# Fibernet.net
KiCad netlist of a schematic drawn in Altium Designer
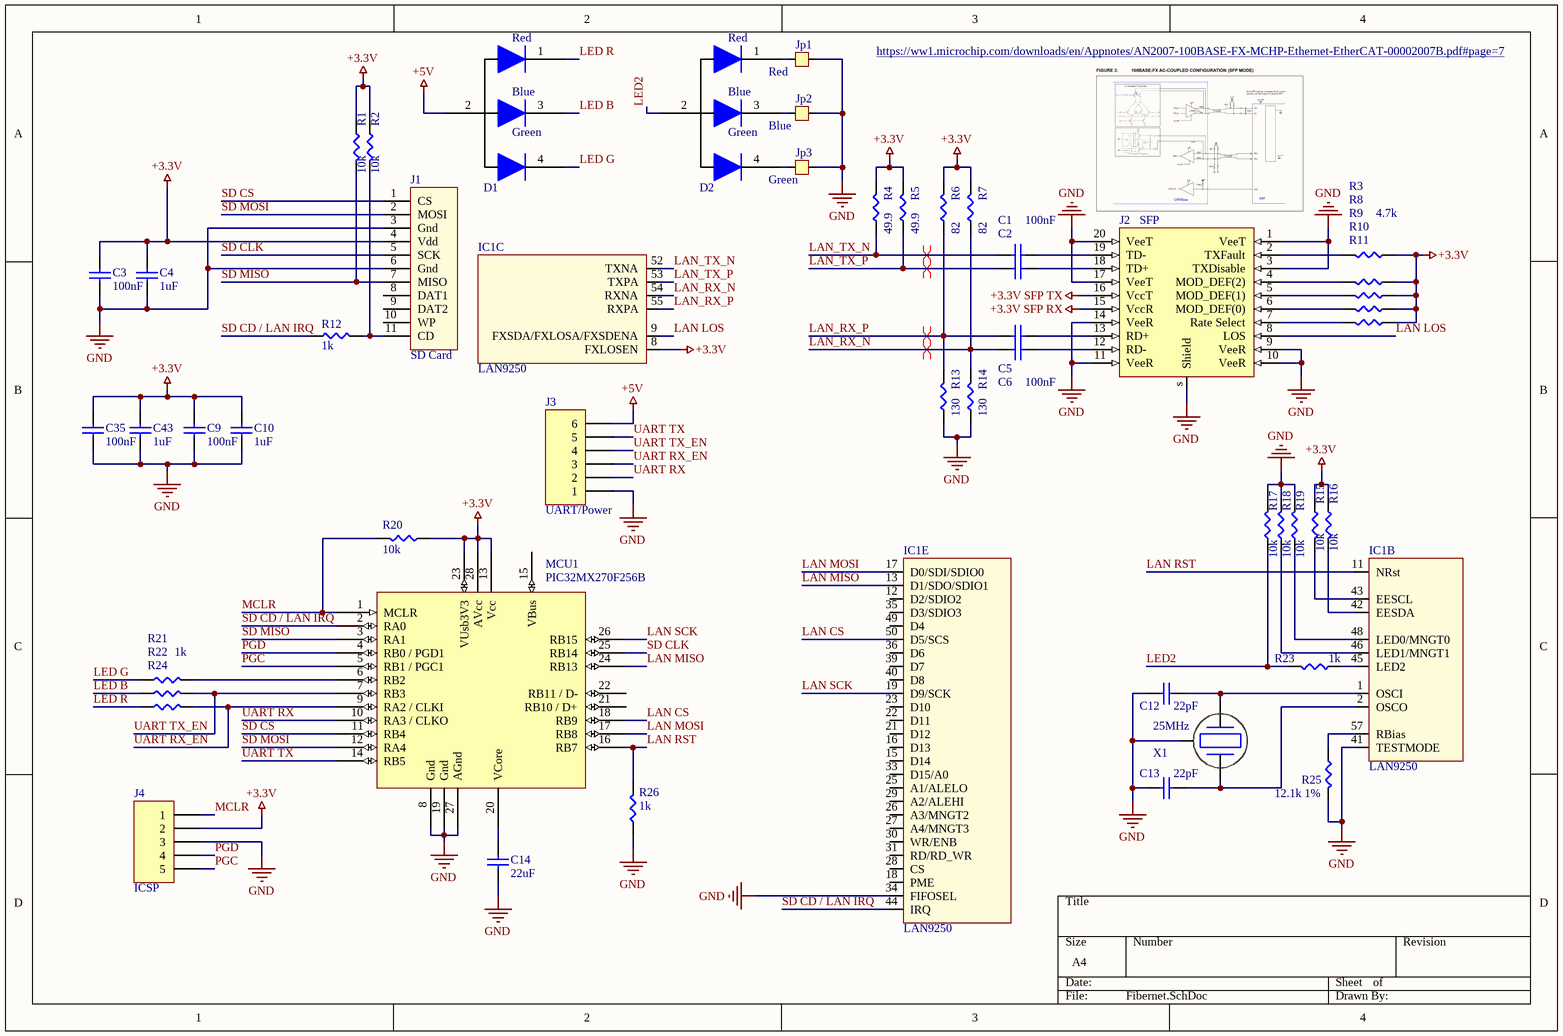
[diagram p0: Fibernet.SchDoc]

(export (version "E")
  (design (tool "Eeschema 10.0.6"))
  (components
    (comp (ref "C1") (value "100nF") (footprint "0402") (libsource (lib "stdLib") (part "Cap")))
    (comp (ref "C2") (value "100nF") (footprint "0402") (libsource (lib "stdLib") (part "Cap")))
    (comp (ref "C3") (value "100nF") (footprint "0402") (libsource (lib "stdLib") (part "Cap")))
    (comp (ref "C4") (value "1uF") (footprint "0402") (libsource (lib "stdLib") (part "Cap")))
    (comp (ref "C5") (value "100nF") (footprint "0402") (libsource (lib "stdLib") (part "Cap")))
    (comp (ref "C6") (value "100nF") (footprint "0402") (libsource (lib "stdLib") (part "Cap")))
    (comp (ref "C9") (value "100nF") (footprint "0402") (libsource (lib "stdLib") (part "Cap")))
    (comp (ref "C10") (value "1uF") (footprint "0402") (libsource (lib "stdLib") (part "Cap")))
    (comp (ref "C12") (value "22pF") (footprint "0402") (libsource (lib "stdLib") (part "Cap")))
    (comp (ref "C13") (value "22pF") (footprint "0402") (libsource (lib "stdLib") (part "Cap")))
    (comp (ref "C14") (value "22uF") (footprint "0603") (libsource (lib "stdLib") (part "Cap")))
    (comp (ref "C35") (value "100nF") (footprint "0402") (libsource (lib "stdLib") (part "Cap")))
    (comp (ref "C43") (value "1uF") (footprint "0402") (libsource (lib "stdLib") (part "Cap")))
    (comp (ref "D1")
      (value "RGB LED Common anode")
      (footprint "1411")
      (description "RGB LED Invered")
      (libsource (lib "stdLib") (part "RGB LED"))
    )
    (comp (ref "D2")
      (value "RGB LED Common anode")
      (footprint "1411")
      (description "RGB LED Invered")
      (libsource (lib "stdLib") (part "RGB LED"))
    )
    (comp (ref "IC1")
      (value "LAN9250")
      (footprint "QFN64")
      (description "10/100 Ethernet controller & PHY")
      (libsource (lib "") (part "LAN9250_1"))
    )
    (comp (ref "J1") (value "SD Card") (footprint "MEM2075") (libsource (lib "stdLib") (part "SD Card")))
    (comp (ref "J2")
      (value "SFP")
      (footprint "SFP Con and Cage")
      (description "SFP Connector with cage")
      (libsource (lib "stdLib") (part "SFP Connector"))
    )
    (comp (ref "J3")
      (value "UART/Power")
      (footprint "HDR1X6")
      (description "Header, 6-Pin")
      (fields (field (name "PUBLISHER") "Altium Limited"))
      (libsource (lib "Miscellaneous Connectors") (part "Header 6"))
    )
    (comp (ref "J4")
      (value "ICSP")
      (footprint "HDR1X5")
      (description "Header, 5-Pin")
      (fields (field (name "PUBLISHER") "Altium Limited"))
      (libsource (lib "Miscellaneous Connectors") (part "Header 5"))
    )
    (comp (ref "Jp1") (value "Red") (footprint "PCB Jumper NO") (libsource (lib "stdLib") (part "Jumper")))
    (comp (ref "Jp2") (value "Blue") (footprint "PCB Jumper NO") (libsource (lib "stdLib") (part "Jumper")))
    (comp (ref "Jp3") (value "Green") (footprint "PCB Jumper NO") (libsource (lib "stdLib") (part "Jumper")))
    (comp (ref "MCU1")
      (value "PIC32MX270F256B")
      (footprint "TSSOP28_Wide")
      (description "32Bit pic with usb")
      (libsource (lib "stdLib") (part "PIC32MX2xxFxxxB"))
    )
    (comp (ref "R1") (value "10k") (footprint "0402") (libsource (lib "stdLib") (part "Resistor")))
    (comp (ref "R2") (value "10k") (footprint "0402") (libsource (lib "stdLib") (part "Resistor")))
    (comp (ref "R3") (value "4.7k") (footprint "0402") (libsource (lib "stdLib") (part "Resistor")))
    (comp (ref "R4") (value "49.9") (footprint "0402") (libsource (lib "stdLib") (part "Resistor")))
    (comp (ref "R5") (value "49.9") (footprint "0402") (libsource (lib "stdLib") (part "Resistor")))
    (comp (ref "R6") (value "82") (footprint "0402") (libsource (lib "stdLib") (part "Resistor")))
    (comp (ref "R7") (value "82") (footprint "0402") (libsource (lib "stdLib") (part "Resistor")))
    (comp (ref "R8") (value "4.7k") (footprint "0402") (libsource (lib "stdLib") (part "Resistor")))
    (comp (ref "R9") (value "4.7k") (footprint "0402") (libsource (lib "stdLib") (part "Resistor")))
    (comp (ref "R10") (value "4.7k") (footprint "0402") (libsource (lib "stdLib") (part "Resistor")))
    (comp (ref "R11") (value "4.7k") (footprint "0402") (libsource (lib "stdLib") (part "Resistor")))
    (comp (ref "R12") (value "1k") (footprint "0402") (libsource (lib "stdLib") (part "Resistor")))
    (comp (ref "R13") (value "130") (footprint "0402") (libsource (lib "stdLib") (part "Resistor")))
    (comp (ref "R14") (value "130") (footprint "0402") (libsource (lib "stdLib") (part "Resistor")))
    (comp (ref "R15") (value "10k") (footprint "0402") (libsource (lib "stdLib") (part "Resistor")))
    (comp (ref "R16") (value "10k") (footprint "0402") (libsource (lib "stdLib") (part "Resistor")))
    (comp (ref "R17") (value "10k") (footprint "0402") (libsource (lib "stdLib") (part "Resistor")))
    (comp (ref "R18") (value "10k") (footprint "0402") (libsource (lib "stdLib") (part "Resistor")))
    (comp (ref "R19") (value "10k") (footprint "0402") (libsource (lib "stdLib") (part "Resistor")))
    (comp (ref "R20") (value "10k") (footprint "0402") (libsource (lib "stdLib") (part "Resistor")))
    (comp (ref "R21") (value "1k") (footprint "0402") (libsource (lib "stdLib") (part "Resistor")))
    (comp (ref "R22") (value "1k") (footprint "0402") (libsource (lib "stdLib") (part "Resistor")))
    (comp (ref "R23") (value "1k") (footprint "0402") (libsource (lib "stdLib") (part "Resistor")))
    (comp (ref "R24") (value "1k") (footprint "0402") (libsource (lib "stdLib") (part "Resistor")))
    (comp (ref "R25") (value "12.1k 1%") (footprint "0402") (libsource (lib "stdLib") (part "Resistor")))
    (comp (ref "R26") (value "1k") (footprint "0402") (libsource (lib "stdLib") (part "Resistor")))
    (comp (ref "X1")
      (value "25MHz")
      (footprint "ECS-3225MV Oscillator")
      (libsource (lib "stdLib") (part "Quarz crystal"))
    )
  )
  (nets
    (net (code "1") (name "+3.3V") (class "Default")
      (node (ref "C10") (pin "2") (pinfunction "2_2") (pintype "passive"))
      (node (ref "C3") (pin "2") (pinfunction "2_2") (pintype "passive"))
      (node (ref "C35") (pin "2") (pinfunction "2_2") (pintype "passive"))
      (node (ref "C4") (pin "2") (pinfunction "2_2") (pintype "passive"))
      (node (ref "C43") (pin "2") (pinfunction "2_2") (pintype "passive"))
      (node (ref "C9") (pin "2") (pinfunction "2_2") (pintype "passive"))
      (node (ref "IC1") (pin "8") (pinfunction "FXLOSEN_8") (pintype "passive"))
      (node (ref "J1") (pin "4") (pinfunction "Vdd_4") (pintype "passive"))
      (node (ref "J4") (pin "2") (pinfunction "2_2") (pintype "passive"))
      (node (ref "MCU1") (pin "13") (pinfunction "Vcc_13") (pintype "power_in"))
      (node (ref "MCU1") (pin "23") (pinfunction "VUsb3V3_23") (pintype "bidirectional"))
      (node (ref "MCU1") (pin "28") (pinfunction "AVcc_28") (pintype "power_in"))
      (node (ref "R1") (pin "1") (pinfunction "1_1") (pintype "passive"))
      (node (ref "R10") (pin "2") (pinfunction "2_2") (pintype "passive"))
      (node (ref "R11") (pin "2") (pinfunction "2_2") (pintype "passive"))
      (node (ref "R15") (pin "1") (pinfunction "1_1") (pintype "passive"))
      (node (ref "R16") (pin "1") (pinfunction "1_1") (pintype "passive"))
      (node (ref "R2") (pin "1") (pinfunction "1_1") (pintype "passive"))
      (node (ref "R20") (pin "1") (pinfunction "1_1") (pintype "passive"))
      (node (ref "R3") (pin "2") (pinfunction "2_2") (pintype "passive"))
      (node (ref "R4") (pin "1") (pinfunction "1_1") (pintype "passive"))
      (node (ref "R5") (pin "1") (pinfunction "1_1") (pintype "passive"))
      (node (ref "R6") (pin "1") (pinfunction "1_1") (pintype "passive"))
      (node (ref "R7") (pin "1") (pinfunction "1_1") (pintype "passive"))
      (node (ref "R8") (pin "2") (pinfunction "2_2") (pintype "passive"))
      (node (ref "R9") (pin "2") (pinfunction "2_2") (pintype "passive"))
    )
    (net (code "2") (name "+3.3V SFP RX") (class "Default")
      (node (ref "J2") (pin "15") (pinfunction "VccR_15") (pintype "input"))
    )
    (net (code "3") (name "+3.3V SFP TX") (class "Default")
      (node (ref "J2") (pin "16") (pinfunction "VccT_16") (pintype "input"))
    )
    (net (code "4") (name "+5V") (class "Default")
      (node (ref "D1") (pin "2") (pintype "passive"))
      (node (ref "J3") (pin "6") (pinfunction "6_6") (pintype "passive"))
    )
    (net (code "5") (name "/LAN CS") (class "Default")
      (node (ref "IC1") (pin "50") (pinfunction "D5/SCS_50") (pintype "passive"))
      (node (ref "MCU1") (pin "18") (pinfunction "RB9_18") (pintype "bidirectional"))
    )
    (net (code "6") (name "/LAN LOS") (class "Default")
      (node (ref "IC1") (pin "9") (pinfunction "FXSDA/FXLOSA/FXSDENA_9") (pintype "passive"))
      (node (ref "J2") (pin "8") (pinfunction "LOS_8") (pintype "input"))
    )
    (net (code "7") (name "/LAN MISO") (class "Default")
      (node (ref "IC1") (pin "13") (pinfunction "D1/SDO/SDIO1_13") (pintype "passive"))
      (node (ref "MCU1") (pin "24") (pinfunction "RB13_24") (pintype "bidirectional"))
    )
    (net (code "8") (name "/LAN MOSI") (class "Default")
      (node (ref "IC1") (pin "17") (pinfunction "D0/SDI/SDIO0_17") (pintype "passive"))
      (node (ref "MCU1") (pin "17") (pinfunction "RB8_17") (pintype "bidirectional"))
    )
    (net (code "9") (name "/LAN RST") (class "Default")
      (node (ref "IC1") (pin "11") (pinfunction "NRst_11") (pintype "passive"))
      (node (ref "MCU1") (pin "16") (pinfunction "RB7_16") (pintype "bidirectional"))
      (node (ref "R26") (pin "1") (pinfunction "1_1") (pintype "passive"))
    )
    (net (code "10") (name "/LAN SCK") (class "Default")
      (node (ref "IC1") (pin "19") (pinfunction "D9/SCK_19") (pintype "passive"))
      (node (ref "MCU1") (pin "26") (pinfunction "RB15_26") (pintype "bidirectional"))
    )
    (net (code "11") (name "/LAN_RX_N") (class "Default")
      (node (ref "C6") (pin "1") (pinfunction "1_1") (pintype "passive"))
      (node (ref "IC1") (pin "54") (pinfunction "RXNA_54") (pintype "passive"))
      (node (ref "R14") (pin "1") (pinfunction "1_1") (pintype "passive"))
      (node (ref "R7") (pin "2") (pinfunction "2_2") (pintype "passive"))
    )
    (net (code "12") (name "/LAN_RX_P") (class "Default")
      (node (ref "C5") (pin "1") (pinfunction "1_1") (pintype "passive"))
      (node (ref "IC1") (pin "55") (pinfunction "RXPA_55") (pintype "passive"))
      (node (ref "R13") (pin "1") (pinfunction "1_1") (pintype "passive"))
      (node (ref "R6") (pin "2") (pinfunction "2_2") (pintype "passive"))
    )
    (net (code "13") (name "/LAN_TX_N") (class "Default")
      (node (ref "C1") (pin "1") (pinfunction "1_1") (pintype "passive"))
      (node (ref "IC1") (pin "52") (pinfunction "TXNA_52") (pintype "passive"))
      (node (ref "R4") (pin "2") (pinfunction "2_2") (pintype "passive"))
    )
    (net (code "14") (name "/LAN_TX_P") (class "Default")
      (node (ref "C2") (pin "1") (pinfunction "1_1") (pintype "passive"))
      (node (ref "IC1") (pin "53") (pinfunction "TXPA_53") (pintype "passive"))
      (node (ref "R5") (pin "2") (pinfunction "2_2") (pintype "passive"))
    )
    (net (code "15") (name "/LED B") (class "Default")
      (node (ref "D1") (pin "3") (pintype "passive"))
      (node (ref "R22") (pin "2") (pinfunction "2_2") (pintype "passive"))
    )
    (net (code "16") (name "/LED G") (class "Default")
      (node (ref "D1") (pin "4") (pintype "passive"))
      (node (ref "R21") (pin "2") (pinfunction "2_2") (pintype "passive"))
    )
    (net (code "17") (name "/LED R") (class "Default")
      (node (ref "D1") (pin "1") (pintype "passive"))
      (node (ref "R24") (pin "2") (pinfunction "2_2") (pintype "passive"))
    )
    (net (code "18") (name "/LED2") (class "Default")
      (node (ref "D2") (pin "2") (pintype "passive"))
      (node (ref "R17") (pin "2") (pinfunction "2_2") (pintype "passive"))
      (node (ref "R23") (pin "1") (pinfunction "1_1") (pintype "passive"))
    )
    (net (code "19") (name "/MCLR") (class "Default")
      (node (ref "J4") (pin "1") (pinfunction "1_1") (pintype "passive"))
      (node (ref "MCU1") (pin "1") (pinfunction "MCLR_1") (pintype "input"))
      (node (ref "R20") (pin "2") (pinfunction "2_2") (pintype "passive"))
    )
    (net (code "20") (name "/PGC") (class "Default")
      (node (ref "J4") (pin "5") (pinfunction "5_5") (pintype "passive"))
      (node (ref "MCU1") (pin "5") (pinfunction "RB1_/_PGC1_5") (pintype "bidirectional"))
    )
    (net (code "21") (name "/PGD") (class "Default")
      (node (ref "J4") (pin "4") (pinfunction "4_4") (pintype "passive"))
      (node (ref "MCU1") (pin "4") (pinfunction "RB0_/_PGD1_4") (pintype "bidirectional"))
    )
    (net (code "22") (name "/SD CD {slash} LAN IRQ") (class "Default")
      (node (ref "IC1") (pin "44") (pinfunction "IRQ_44") (pintype "passive"))
      (node (ref "MCU1") (pin "2") (pinfunction "RA0_2") (pintype "bidirectional"))
      (node (ref "R12") (pin "1") (pinfunction "1_1") (pintype "passive"))
    )
    (net (code "23") (name "/SD CLK") (class "Default")
      (node (ref "J1") (pin "5") (pinfunction "SCK_5") (pintype "passive"))
      (node (ref "MCU1") (pin "25") (pinfunction "RB14_25") (pintype "bidirectional"))
    )
    (net (code "24") (name "/SD CS") (class "Default")
      (node (ref "J1") (pin "1") (pinfunction "CS_1") (pintype "passive"))
      (node (ref "MCU1") (pin "11") (pinfunction "RB4_11") (pintype "bidirectional"))
    )
    (net (code "25") (name "/SD MISO") (class "Default")
      (node (ref "J1") (pin "7") (pinfunction "MISO_7") (pintype "passive"))
      (node (ref "MCU1") (pin "3") (pinfunction "RA1_3") (pintype "bidirectional"))
      (node (ref "R1") (pin "2") (pinfunction "2_2") (pintype "passive"))
    )
    (net (code "26") (name "/SD MOSI") (class "Default")
      (node (ref "J1") (pin "2") (pinfunction "MOSI_2") (pintype "passive"))
      (node (ref "MCU1") (pin "12") (pinfunction "RA4_12") (pintype "bidirectional"))
    )
    (net (code "27") (name "/UART RX") (class "Default")
      (node (ref "J3") (pin "2") (pinfunction "2_2") (pintype "passive"))
      (node (ref "MCU1") (pin "10") (pinfunction "RA3_/_CLKO_10") (pintype "bidirectional"))
    )
    (net (code "28") (name "/UART RX_EN") (class "Default")
      (node (ref "J3") (pin "3") (pinfunction "3_3") (pintype "passive"))
      (node (ref "MCU1") (pin "9") (pinfunction "RA2_/_CLKI_9") (pintype "bidirectional"))
      (node (ref "R24") (pin "1") (pinfunction "1_1") (pintype "passive"))
    )
    (net (code "29") (name "/UART TX") (class "Default")
      (node (ref "J3") (pin "5") (pinfunction "5_5") (pintype "passive"))
      (node (ref "MCU1") (pin "14") (pinfunction "RB5_14") (pintype "bidirectional"))
    )
    (net (code "30") (name "/UART TX_EN") (class "Default")
      (node (ref "J3") (pin "4") (pinfunction "4_4") (pintype "passive"))
      (node (ref "MCU1") (pin "7") (pinfunction "RB3_7") (pintype "bidirectional"))
      (node (ref "R22") (pin "1") (pinfunction "1_1") (pintype "passive"))
    )
    (net (code "31") (name "GND") (class "Default")
      (node (ref "C10") (pin "1") (pinfunction "1_1") (pintype "passive"))
      (node (ref "C12") (pin "1") (pinfunction "1_1") (pintype "passive"))
      (node (ref "C13") (pin "1") (pinfunction "1_1") (pintype "passive"))
      (node (ref "C14") (pin "1") (pinfunction "1_1") (pintype "passive"))
      (node (ref "C3") (pin "1") (pinfunction "1_1") (pintype "passive"))
      (node (ref "C35") (pin "1") (pinfunction "1_1") (pintype "passive"))
      (node (ref "C4") (pin "1") (pinfunction "1_1") (pintype "passive"))
      (node (ref "C43") (pin "1") (pinfunction "1_1") (pintype "passive"))
      (node (ref "C9") (pin "1") (pinfunction "1_1") (pintype "passive"))
      (node (ref "IC1") (pin "34") (pinfunction "FIFOSEL_34") (pintype "passive"))
      (node (ref "IC1") (pin "41") (pinfunction "TESTMODE_41") (pintype "passive"))
      (node (ref "J1") (pin "3") (pinfunction "Gnd_3") (pintype "passive"))
      (node (ref "J1") (pin "6") (pinfunction "Gnd_6") (pintype "passive"))
      (node (ref "J2") (pin "1") (pinfunction "VeeT_1") (pintype "input"))
      (node (ref "J2") (pin "10") (pinfunction "VeeR_10") (pintype "input"))
      (node (ref "J2") (pin "11") (pinfunction "VeeR_11") (pintype "input"))
      (node (ref "J2") (pin "14") (pinfunction "VeeR_14") (pintype "input"))
      (node (ref "J2") (pin "17") (pinfunction "VeeT_17") (pintype "input"))
      (node (ref "J2") (pin "20") (pinfunction "VeeT_20") (pintype "input"))
      (node (ref "J2") (pin "3") (pinfunction "TXDisable_3") (pintype "input"))
      (node (ref "J2") (pin "9") (pinfunction "VeeR_9") (pintype "input"))
      (node (ref "J2") (pin "s") (pinfunction "Shield_s") (pintype "passive"))
      (node (ref "J3") (pin "1") (pinfunction "1_1") (pintype "passive"))
      (node (ref "J4") (pin "3") (pinfunction "3_3") (pintype "passive"))
      (node (ref "Jp1") (pin "2") (pinfunction "2_2") (pintype "passive"))
      (node (ref "Jp2") (pin "2") (pinfunction "2_2") (pintype "passive"))
      (node (ref "Jp3") (pin "2") (pinfunction "2_2") (pintype "passive"))
      (node (ref "MCU1") (pin "19") (pinfunction "Gnd_19") (pintype "power_in"))
      (node (ref "MCU1") (pin "27") (pinfunction "AGnd_27") (pintype "power_in"))
      (node (ref "MCU1") (pin "8") (pinfunction "Gnd_8") (pintype "power_in"))
      (node (ref "R13") (pin "2") (pinfunction "2_2") (pintype "passive"))
      (node (ref "R14") (pin "2") (pinfunction "2_2") (pintype "passive"))
      (node (ref "R17") (pin "1") (pinfunction "1_1") (pintype "passive"))
      (node (ref "R18") (pin "1") (pinfunction "1_1") (pintype "passive"))
      (node (ref "R19") (pin "1") (pinfunction "1_1") (pintype "passive"))
      (node (ref "R25") (pin "1") (pinfunction "1_1") (pintype "passive"))
      (node (ref "R26") (pin "2") (pinfunction "2_2") (pintype "passive"))
      (node (ref "X1") (pin "3") (pinfunction "Shield_3") (pintype "passive"))
    )
    (net (code "32") (name "Net-(D2-Pad1)") (class "Default")
      (node (ref "D2") (pin "1") (pintype "passive"))
      (node (ref "Jp1") (pin "1") (pinfunction "1_1") (pintype "passive"))
    )
    (net (code "33") (name "Net-(D2-Pad3)") (class "Default")
      (node (ref "D2") (pin "3") (pintype "passive"))
      (node (ref "Jp2") (pin "1") (pinfunction "1_1") (pintype "passive"))
    )
    (net (code "34") (name "Net-(D2-Pad4)") (class "Default")
      (node (ref "D2") (pin "4") (pintype "passive"))
      (node (ref "Jp3") (pin "1") (pinfunction "1_1") (pintype "passive"))
    )
    (net (code "35") (name "Net-(IC1B-EESCL)") (class "Default")
      (node (ref "IC1") (pin "43") (pinfunction "EESCL_43") (pintype "passive"))
      (node (ref "R15") (pin "2") (pinfunction "2_2") (pintype "passive"))
    )
    (net (code "36") (name "Net-(IC1B-EESDA)") (class "Default")
      (node (ref "IC1") (pin "42") (pinfunction "EESDA_42") (pintype "passive"))
      (node (ref "R16") (pin "2") (pinfunction "2_2") (pintype "passive"))
    )
    (net (code "37") (name "Net-(IC1B-LED0{slash}MNGT0)") (class "Default")
      (node (ref "IC1") (pin "48") (pinfunction "LED0/MNGT0_48") (pintype "passive"))
      (node (ref "R19") (pin "2") (pinfunction "2_2") (pintype "passive"))
    )
    (net (code "38") (name "Net-(IC1B-LED1{slash}MNGT1)") (class "Default")
      (node (ref "IC1") (pin "46") (pinfunction "LED1/MNGT1_46") (pintype "passive"))
      (node (ref "R18") (pin "2") (pinfunction "2_2") (pintype "passive"))
    )
    (net (code "39") (name "Net-(IC1B-LED2)") (class "Default")
      (node (ref "IC1") (pin "45") (pinfunction "LED2_45") (pintype "passive"))
      (node (ref "R23") (pin "2") (pinfunction "2_2") (pintype "passive"))
    )
    (net (code "40") (name "Net-(IC1B-OSCI)") (class "Default")
      (node (ref "C12") (pin "2") (pinfunction "2_2") (pintype "passive"))
      (node (ref "IC1") (pin "1") (pinfunction "OSCI_1") (pintype "passive"))
      (node (ref "X1") (pin "2") (pinfunction "24_2") (pintype "passive"))
    )
    (net (code "41") (name "Net-(IC1B-OSCO)") (class "Default")
      (node (ref "C13") (pin "2") (pinfunction "2_2") (pintype "passive"))
      (node (ref "IC1") (pin "2") (pinfunction "OSCO_2") (pintype "passive"))
      (node (ref "X1") (pin "1") (pinfunction "23_1") (pintype "passive"))
    )
    (net (code "42") (name "Net-(IC1B-RBias)") (class "Default")
      (node (ref "IC1") (pin "57") (pinfunction "RBias_57") (pintype "passive"))
      (node (ref "R25") (pin "2") (pinfunction "2_2") (pintype "passive"))
    )
    (net (code "43") (name "Net-(J1-CD)") (class "Default")
      (node (ref "J1") (pin "11") (pinfunction "CD_11") (pintype "passive"))
      (node (ref "R12") (pin "2") (pinfunction "2_2") (pintype "passive"))
      (node (ref "R2") (pin "2") (pinfunction "2_2") (pintype "passive"))
    )
    (net (code "44") (name "Net-(J2-MOD_DEF(0))") (class "Default")
      (node (ref "J2") (pin "6") (pinfunction "MOD_DEF(0)_6") (pintype "input"))
      (node (ref "R9") (pin "1") (pinfunction "1_1") (pintype "passive"))
    )
    (net (code "45") (name "Net-(J2-MOD_DEF(1))") (class "Default")
      (node (ref "J2") (pin "5") (pinfunction "MOD_DEF(1)_5") (pintype "input"))
      (node (ref "R8") (pin "1") (pinfunction "1_1") (pintype "passive"))
    )
    (net (code "46") (name "Net-(J2-MOD_DEF(2))") (class "Default")
      (node (ref "J2") (pin "4") (pinfunction "MOD_DEF(2)_4") (pintype "input"))
      (node (ref "R10") (pin "1") (pinfunction "1_1") (pintype "passive"))
    )
    (net (code "47") (name "Net-(J2-RD+)") (class "Default")
      (node (ref "C5") (pin "2") (pinfunction "2_2") (pintype "passive"))
      (node (ref "J2") (pin "13") (pinfunction "RD+_13") (pintype "input"))
    )
    (net (code "48") (name "Net-(J2-RD-)") (class "Default")
      (node (ref "C6") (pin "2") (pinfunction "2_2") (pintype "passive"))
      (node (ref "J2") (pin "12") (pinfunction "RD-_12") (pintype "input"))
    )
    (net (code "49") (name "Net-(J2-Rate_Select)") (class "Default")
      (node (ref "J2") (pin "7") (pinfunction "Rate_Select_7") (pintype "input"))
      (node (ref "R11") (pin "1") (pinfunction "1_1") (pintype "passive"))
    )
    (net (code "50") (name "Net-(J2-TD+)") (class "Default")
      (node (ref "C2") (pin "2") (pinfunction "2_2") (pintype "passive"))
      (node (ref "J2") (pin "18") (pinfunction "TD+_18") (pintype "input"))
    )
    (net (code "51") (name "Net-(J2-TD-)") (class "Default")
      (node (ref "C1") (pin "2") (pinfunction "2_2") (pintype "passive"))
      (node (ref "J2") (pin "19") (pinfunction "TD-_19") (pintype "input"))
    )
    (net (code "52") (name "Net-(J2-TXFault)") (class "Default")
      (node (ref "J2") (pin "2") (pinfunction "TXFault_2") (pintype "input"))
      (node (ref "R3") (pin "1") (pinfunction "1_1") (pintype "passive"))
    )
    (net (code "53") (name "Net-(MCU1-RB2)") (class "Default")
      (node (ref "MCU1") (pin "6") (pinfunction "RB2_6") (pintype "bidirectional"))
      (node (ref "R21") (pin "1") (pinfunction "1_1") (pintype "passive"))
    )
    (net (code "54") (name "Net-(MCU1-VCore)") (class "Default")
      (node (ref "C14") (pin "2") (pinfunction "2_2") (pintype "passive"))
      (node (ref "MCU1") (pin "20") (pinfunction "VCore_20") (pintype "power_in"))
    )
    (net (code "55") (name "unconnected-(IC1E-A1{slash}ALELO-Pad25)") (class "Default")
      (node (ref "IC1") (pin "25") (pinfunction "A1/ALELO_25") (pintype "passive"))
    )
    (net (code "56") (name "unconnected-(IC1E-A2{slash}ALEHI-Pad29)") (class "Default")
      (node (ref "IC1") (pin "29") (pinfunction "A2/ALEHI_29") (pintype "passive"))
    )
    (net (code "57") (name "unconnected-(IC1E-A3{slash}MNGT2-Pad26)") (class "Default")
      (node (ref "IC1") (pin "26") (pinfunction "A3/MNGT2_26") (pintype "passive"))
    )
    (net (code "58") (name "unconnected-(IC1E-A4{slash}MNGT3-Pad27)") (class "Default")
      (node (ref "IC1") (pin "27") (pinfunction "A4/MNGT3_27") (pintype "passive"))
    )
    (net (code "59") (name "unconnected-(IC1E-CS-Pad28)") (class "Default")
      (node (ref "IC1") (pin "28") (pinfunction "CS_28") (pintype "passive"))
    )
    (net (code "60") (name "unconnected-(IC1E-D2{slash}SDIO2-Pad12)") (class "Default")
      (node (ref "IC1") (pin "12") (pinfunction "D2/SDIO2_12") (pintype "passive"))
    )
    (net (code "61") (name "unconnected-(IC1E-D3{slash}SDIO3-Pad35)") (class "Default")
      (node (ref "IC1") (pin "35") (pinfunction "D3/SDIO3_35") (pintype "passive"))
    )
    (net (code "62") (name "unconnected-(IC1E-D4-Pad49)") (class "Default")
      (node (ref "IC1") (pin "49") (pinfunction "D4_49") (pintype "passive"))
    )
    (net (code "63") (name "unconnected-(IC1E-D6-Pad36)") (class "Default")
      (node (ref "IC1") (pin "36") (pinfunction "D6_36") (pintype "passive"))
    )
    (net (code "64") (name "unconnected-(IC1E-D7-Pad39)") (class "Default")
      (node (ref "IC1") (pin "39") (pinfunction "D7_39") (pintype "passive"))
    )
    (net (code "65") (name "unconnected-(IC1E-D8-Pad40)") (class "Default")
      (node (ref "IC1") (pin "40") (pinfunction "D8_40") (pintype "passive"))
    )
    (net (code "66") (name "unconnected-(IC1E-D10-Pad23)") (class "Default")
      (node (ref "IC1") (pin "23") (pinfunction "D10_23") (pintype "passive"))
    )
    (net (code "67") (name "unconnected-(IC1E-D11-Pad22)") (class "Default")
      (node (ref "IC1") (pin "22") (pinfunction "D11_22") (pintype "passive"))
    )
    (net (code "68") (name "unconnected-(IC1E-D12-Pad21)") (class "Default")
      (node (ref "IC1") (pin "21") (pinfunction "D12_21") (pintype "passive"))
    )
    (net (code "69") (name "unconnected-(IC1E-D13-Pad16)") (class "Default")
      (node (ref "IC1") (pin "16") (pinfunction "D13_16") (pintype "passive"))
    )
    (net (code "70") (name "unconnected-(IC1E-D14-Pad15)") (class "Default")
      (node (ref "IC1") (pin "15") (pinfunction "D14_15") (pintype "passive"))
    )
    (net (code "71") (name "unconnected-(IC1E-D15{slash}A0-Pad33)") (class "Default")
      (node (ref "IC1") (pin "33") (pinfunction "D15/A0_33") (pintype "passive"))
    )
    (net (code "72") (name "unconnected-(IC1E-PME-Pad18)") (class "Default")
      (node (ref "IC1") (pin "18") (pinfunction "PME_18") (pintype "passive"))
    )
    (net (code "73") (name "unconnected-(IC1E-RD{slash}RD_WR-Pad31)") (class "Default")
      (node (ref "IC1") (pin "31") (pinfunction "RD/RD_WR_31") (pintype "passive"))
    )
    (net (code "74") (name "unconnected-(IC1E-WR{slash}ENB-Pad30)") (class "Default")
      (node (ref "IC1") (pin "30") (pinfunction "WR/ENB_30") (pintype "passive"))
    )
    (net (code "75") (name "unconnected-(J1-DAT1-Pad8)") (class "Default")
      (node (ref "J1") (pin "8") (pinfunction "DAT1_8") (pintype "passive"))
    )
    (net (code "76") (name "unconnected-(J1-DAT2-Pad9)") (class "Default")
      (node (ref "J1") (pin "9") (pinfunction "DAT2_9") (pintype "passive"))
    )
    (net (code "77") (name "unconnected-(J1-WP-Pad10)") (class "Default")
      (node (ref "J1") (pin "10") (pinfunction "WP_10") (pintype "passive"))
    )
    (net (code "78") (name "unconnected-(MCU1-RB10_{slash}_D+-Pad21)") (class "Default")
      (node (ref "MCU1") (pin "21") (pinfunction "RB10_/_D+_21") (pintype "bidirectional"))
    )
    (net (code "79") (name "unconnected-(MCU1-RB11_{slash}_D--Pad22)") (class "Default")
      (node (ref "MCU1") (pin "22") (pinfunction "RB11_/_D-_22") (pintype "bidirectional"))
    )
    (net (code "80") (name "unconnected-(MCU1-VBus-Pad15)") (class "Default")
      (node (ref "MCU1") (pin "15") (pinfunction "VBus_15") (pintype "bidirectional"))
    )
  )
)
